# 4017-7Segment.net
KiCad netlist of a schematic drawn in EAGLE
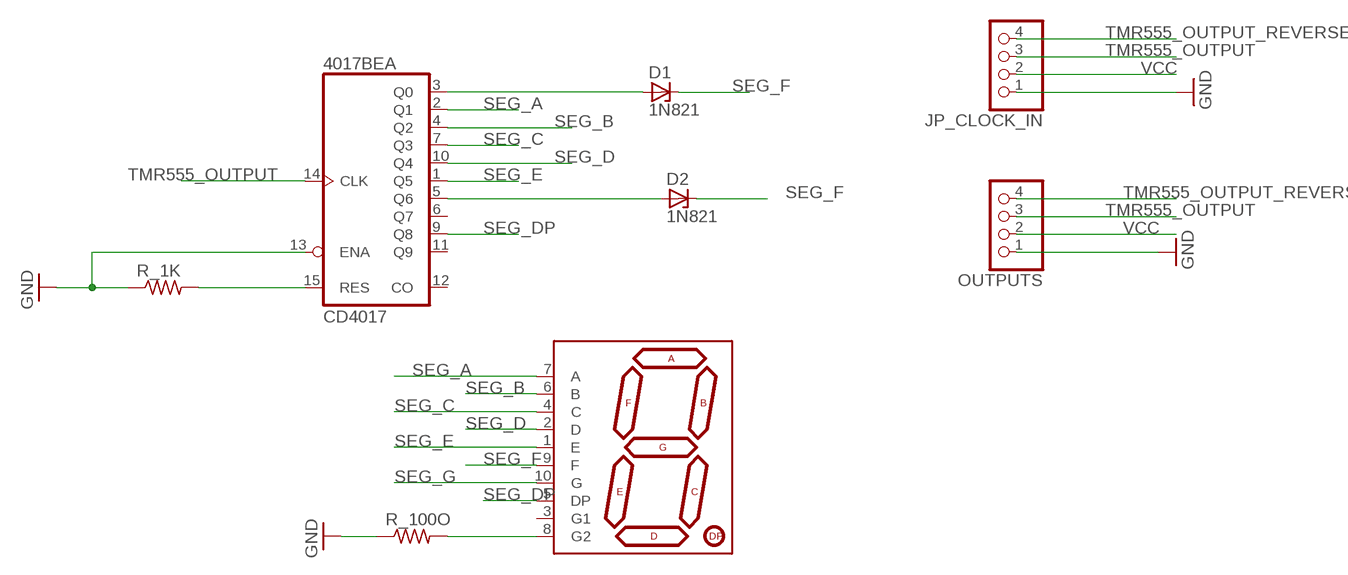
[diagram p0: schematic, sheet 1]

(export (version "E")
  (design (tool "Eeschema 10.0.6"))
  (components
    (comp (ref "4017BE")
      (value "CD4017")
      (footprint "eagle-import:DIL16")
      (libsource (lib "eagle-import") (part "CD4017"))
    )
    (comp (ref "D1")
      (value "1N821")
      (footprint "eagle-import:DO35Z10")
      (libsource (lib "eagle-import") (part "1N821"))
    )
    (comp (ref "D2")
      (value "1N821")
      (footprint "eagle-import:DO35Z10")
      (libsource (lib "eagle-import") (part "1N821"))
    )
    (comp (ref "JP_CLOCK_IN")
      (value "PINHD-1X4")
      (footprint "eagle-import:1X04")
      (libsource (lib "eagle-import") (part "PINHD-1X4"))
    )
    (comp (ref "OUTPUTS")
      (value "PINHD-1X4")
      (footprint "eagle-import:1X04")
      (libsource (lib "eagle-import") (part "PINHD-1X4"))
    )
    (comp (ref "R_1K")
      (value "R-US_R1206")
      (footprint "eagle-import:R1206")
      (libsource (lib "eagle-import") (part "R-US_R1206"))
    )
    (comp (ref "R_100O")
      (value "R-US_R1206")
      (footprint "eagle-import:R1206")
      (libsource (lib "eagle-import") (part "R-US_R1206"))
    )
    (comp (ref "U$1")
      (value "7-SEGMENT-DISPLAYPTH")
      (footprint "eagle-import:7-SEGMENT-DISPLAY")
      (libsource (lib "eagle-import") (part "7-SEGMENT-DISPLAYPTH"))
    )
  )
  (nets
    (net (code "1") (name "/SEG_A") (class "Default")
      (node (ref "4017BE") (pin "2") (pinfunction "Q1_2") (pintype "output"))
      (node (ref "U$1") (pin "7") (pinfunction "A_7") (pintype "bidirectional"))
    )
    (net (code "2") (name "/SEG_B") (class "Default")
      (node (ref "4017BE") (pin "4") (pinfunction "Q2_4") (pintype "output"))
      (node (ref "U$1") (pin "6") (pinfunction "B_6") (pintype "bidirectional"))
    )
    (net (code "3") (name "/SEG_C") (class "Default")
      (node (ref "4017BE") (pin "7") (pinfunction "Q3_7") (pintype "output"))
      (node (ref "U$1") (pin "4") (pinfunction "C_4") (pintype "bidirectional"))
    )
    (net (code "4") (name "/SEG_D") (class "Default")
      (node (ref "4017BE") (pin "10") (pinfunction "Q4_10") (pintype "output"))
      (node (ref "U$1") (pin "2") (pinfunction "D_2") (pintype "bidirectional"))
    )
    (net (code "5") (name "/SEG_DP") (class "Default")
      (node (ref "4017BE") (pin "9") (pinfunction "Q8_9") (pintype "output"))
      (node (ref "U$1") (pin "5") (pinfunction "DP_5") (pintype "bidirectional"))
    )
    (net (code "6") (name "/SEG_E") (class "Default")
      (node (ref "4017BE") (pin "1") (pinfunction "Q5_1") (pintype "output"))
      (node (ref "U$1") (pin "1") (pinfunction "E_1") (pintype "bidirectional"))
    )
    (net (code "7") (name "/SEG_F") (class "Default")
      (node (ref "D1") (pin "C") (pinfunction "C_C") (pintype "passive"))
      (node (ref "D2") (pin "C") (pinfunction "C_C") (pintype "passive"))
      (node (ref "U$1") (pin "9") (pinfunction "F_9") (pintype "bidirectional"))
    )
    (net (code "8") (name "/SEG_G") (class "Default")
      (node (ref "U$1") (pin "10") (pinfunction "G_10") (pintype "bidirectional"))
    )
    (net (code "9") (name "/TMR555_OUTPUT") (class "Default")
      (node (ref "4017BE") (pin "14") (pinfunction "CLK_14") (pintype "input"))
      (node (ref "JP_CLOCK_IN") (pin "3") (pinfunction "3_3") (pintype "passive"))
      (node (ref "OUTPUTS") (pin "3") (pinfunction "3_3") (pintype "passive"))
    )
    (net (code "10") (name "/TMR555_OUTPUT_REVERSE") (class "Default")
      (node (ref "JP_CLOCK_IN") (pin "4") (pinfunction "4_4") (pintype "passive"))
      (node (ref "OUTPUTS") (pin "4") (pinfunction "4_4") (pintype "passive"))
    )
    (net (code "11") (name "/VCC") (class "Default")
      (node (ref "JP_CLOCK_IN") (pin "2") (pinfunction "2_2") (pintype "passive"))
      (node (ref "OUTPUTS") (pin "2") (pinfunction "2_2") (pintype "passive"))
    )
    (net (code "12") (name "GND") (class "Default")
      (node (ref "4017BE") (pin "13") (pinfunction "ENA_13") (pintype "input"))
      (node (ref "JP_CLOCK_IN") (pin "1") (pinfunction "1_1") (pintype "passive"))
      (node (ref "OUTPUTS") (pin "1") (pinfunction "1_1") (pintype "passive"))
      (node (ref "R_100O") (pin "1") (pinfunction "1_1") (pintype "passive"))
      (node (ref "R_1K") (pin "1") (pinfunction "1_1") (pintype "passive"))
    )
    (net (code "13") (name "Net-(4017BEA-Q0)") (class "Default")
      (node (ref "4017BE") (pin "3") (pinfunction "Q0_3") (pintype "output"))
      (node (ref "D1") (pin "A") (pinfunction "A_A") (pintype "passive"))
    )
    (net (code "14") (name "Net-(4017BEA-Q6)") (class "Default")
      (node (ref "4017BE") (pin "5") (pinfunction "Q6_5") (pintype "output"))
      (node (ref "D2") (pin "A") (pinfunction "A_A") (pintype "passive"))
    )
    (net (code "15") (name "Net-(4017BEA-RES)") (class "Default")
      (node (ref "4017BE") (pin "15") (pinfunction "RES_15") (pintype "input"))
      (node (ref "R_1K") (pin "2") (pinfunction "2_2") (pintype "passive"))
    )
    (net (code "16") (name "Net-(U$1-G2)") (class "Default")
      (node (ref "R_100O") (pin "2") (pinfunction "2_2") (pintype "passive"))
      (node (ref "U$1") (pin "8") (pinfunction "G2_8") (pintype "bidirectional"))
    )
    (net (code "17") (name "unconnected-(4017BEA-CO-Pad12)") (class "Default")
      (node (ref "4017BE") (pin "12") (pinfunction "CO_12") (pintype "output"))
    )
    (net (code "18") (name "unconnected-(4017BEA-Q7-Pad6)") (class "Default")
      (node (ref "4017BE") (pin "6") (pinfunction "Q7_6") (pintype "output"))
    )
    (net (code "19") (name "unconnected-(4017BEA-Q9-Pad11)") (class "Default")
      (node (ref "4017BE") (pin "11") (pinfunction "Q9_11") (pintype "output"))
    )
    (net (code "20") (name "unconnected-(U$1-G1-Pad3)") (class "Default")
      (node (ref "U$1") (pin "3") (pinfunction "G1_3") (pintype "bidirectional"))
    )
  )
)
